# PLACA_01.net
KiCad netlist of a schematic drawn in EAGLE
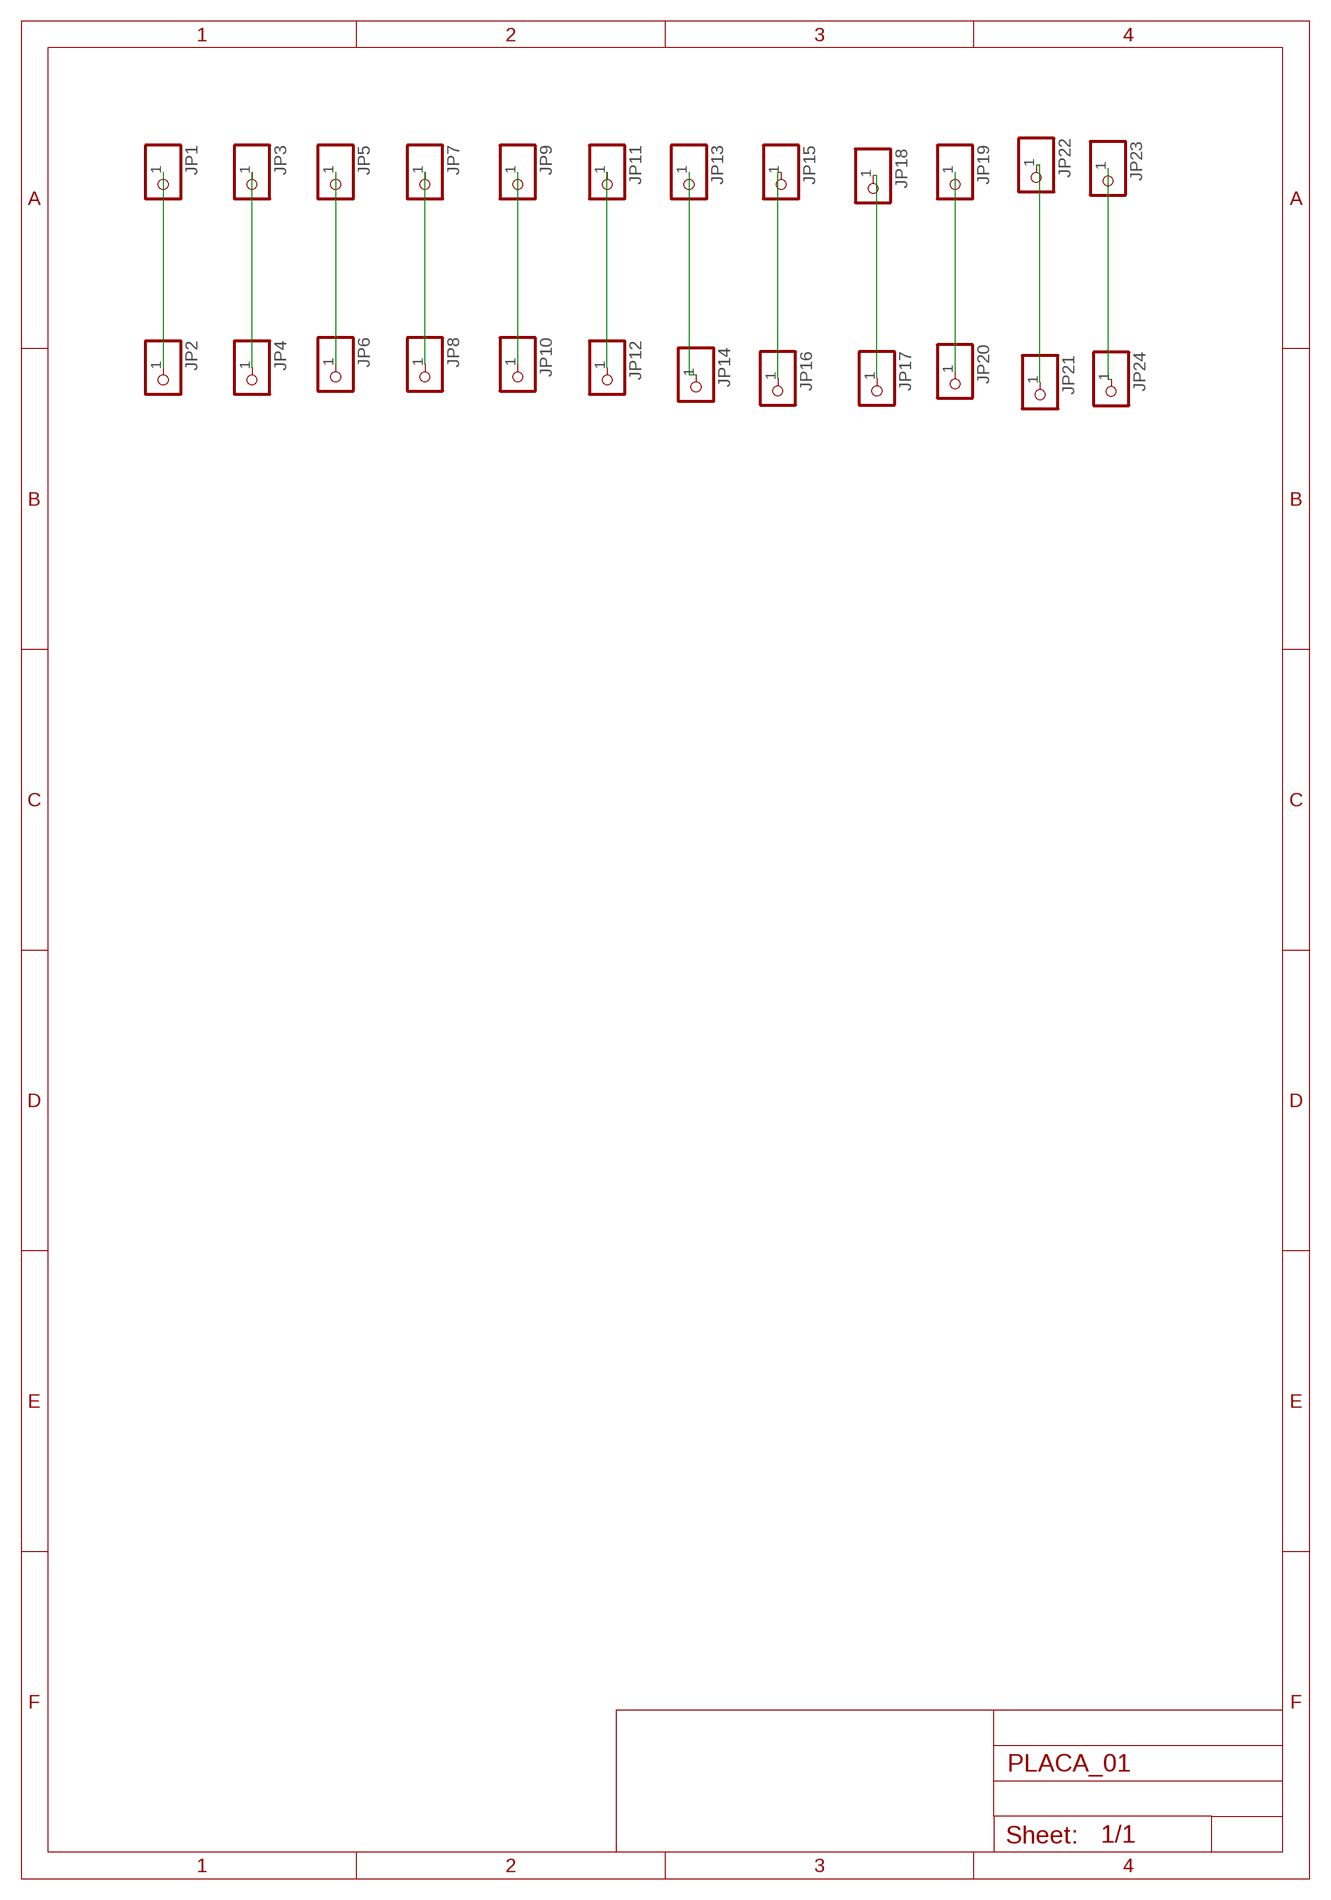
[diagram p0: schematic, sheet 1]

(export (version "E")
  (design (tool "Eeschema 10.0.6"))
  (components
    (comp (ref "JP1")
      (value "PINHD-1X1")
      (footprint "eagle-import:1X01")
      (libsource (lib "eagle-import") (part "PINHD-1X1"))
    )
    (comp (ref "JP2")
      (value "PINHD-1X1")
      (footprint "eagle-import:1X01")
      (libsource (lib "eagle-import") (part "PINHD-1X1"))
    )
    (comp (ref "JP3")
      (value "PINHD-1X1")
      (footprint "eagle-import:1X01")
      (libsource (lib "eagle-import") (part "PINHD-1X1"))
    )
    (comp (ref "JP4")
      (value "PINHD-1X1")
      (footprint "eagle-import:1X01")
      (libsource (lib "eagle-import") (part "PINHD-1X1"))
    )
    (comp (ref "JP5")
      (value "PINHD-1X1")
      (footprint "eagle-import:1X01")
      (libsource (lib "eagle-import") (part "PINHD-1X1"))
    )
    (comp (ref "JP6")
      (value "PINHD-1X1")
      (footprint "eagle-import:1X01")
      (libsource (lib "eagle-import") (part "PINHD-1X1"))
    )
    (comp (ref "JP7")
      (value "PINHD-1X1")
      (footprint "eagle-import:1X01")
      (libsource (lib "eagle-import") (part "PINHD-1X1"))
    )
    (comp (ref "JP8")
      (value "PINHD-1X1")
      (footprint "eagle-import:1X01")
      (libsource (lib "eagle-import") (part "PINHD-1X1"))
    )
    (comp (ref "JP9")
      (value "PINHD-1X1")
      (footprint "eagle-import:1X01")
      (libsource (lib "eagle-import") (part "PINHD-1X1"))
    )
    (comp (ref "JP10")
      (value "PINHD-1X1")
      (footprint "eagle-import:1X01")
      (libsource (lib "eagle-import") (part "PINHD-1X1"))
    )
    (comp (ref "JP11")
      (value "PINHD-1X1")
      (footprint "eagle-import:1X01")
      (libsource (lib "eagle-import") (part "PINHD-1X1"))
    )
    (comp (ref "JP12")
      (value "PINHD-1X1")
      (footprint "eagle-import:1X01")
      (libsource (lib "eagle-import") (part "PINHD-1X1"))
    )
    (comp (ref "JP13")
      (value "PINHD-1X1")
      (footprint "eagle-import:1X01")
      (libsource (lib "eagle-import") (part "PINHD-1X1"))
    )
    (comp (ref "JP14")
      (value "PINHD-1X1")
      (footprint "eagle-import:1X01")
      (libsource (lib "eagle-import") (part "PINHD-1X1"))
    )
    (comp (ref "JP15")
      (value "PINHD-1X1")
      (footprint "eagle-import:1X01")
      (libsource (lib "eagle-import") (part "PINHD-1X1"))
    )
    (comp (ref "JP16")
      (value "PINHD-1X1")
      (footprint "eagle-import:1X01")
      (libsource (lib "eagle-import") (part "PINHD-1X1"))
    )
    (comp (ref "JP17")
      (value "PINHD-1X1")
      (footprint "eagle-import:1X01")
      (libsource (lib "eagle-import") (part "PINHD-1X1"))
    )
    (comp (ref "JP18")
      (value "PINHD-1X1")
      (footprint "eagle-import:1X01")
      (libsource (lib "eagle-import") (part "PINHD-1X1"))
    )
    (comp (ref "JP19")
      (value "PINHD-1X1")
      (footprint "eagle-import:1X01")
      (libsource (lib "eagle-import") (part "PINHD-1X1"))
    )
    (comp (ref "JP20")
      (value "PINHD-1X1")
      (footprint "eagle-import:1X01")
      (libsource (lib "eagle-import") (part "PINHD-1X1"))
    )
    (comp (ref "JP21")
      (value "PINHD-1X1")
      (footprint "eagle-import:1X01")
      (libsource (lib "eagle-import") (part "PINHD-1X1"))
    )
    (comp (ref "JP22")
      (value "PINHD-1X1")
      (footprint "eagle-import:1X01")
      (libsource (lib "eagle-import") (part "PINHD-1X1"))
    )
    (comp (ref "JP23")
      (value "PINHD-1X1")
      (footprint "eagle-import:1X01")
      (libsource (lib "eagle-import") (part "PINHD-1X1"))
    )
    (comp (ref "JP24")
      (value "PINHD-1X1")
      (footprint "eagle-import:1X01")
      (libsource (lib "eagle-import") (part "PINHD-1X1"))
    )
  )
  (nets
    (net (code "1") (name "Net-(JP1-Pad1)") (class "Default")
      (node (ref "JP1") (pin "1") (pinfunction "1_1") (pintype "passive"))
      (node (ref "JP2") (pin "1") (pinfunction "1_1") (pintype "passive"))
    )
    (net (code "2") (name "Net-(JP3-Pad1)") (class "Default")
      (node (ref "JP3") (pin "1") (pinfunction "1_1") (pintype "passive"))
      (node (ref "JP4") (pin "1") (pinfunction "1_1") (pintype "passive"))
    )
    (net (code "3") (name "Net-(JP5-Pad1)") (class "Default")
      (node (ref "JP5") (pin "1") (pinfunction "1_1") (pintype "passive"))
      (node (ref "JP6") (pin "1") (pinfunction "1_1") (pintype "passive"))
    )
    (net (code "4") (name "Net-(JP7-Pad1)") (class "Default")
      (node (ref "JP7") (pin "1") (pinfunction "1_1") (pintype "passive"))
      (node (ref "JP8") (pin "1") (pinfunction "1_1") (pintype "passive"))
    )
    (net (code "5") (name "Net-(JP10-Pad1)") (class "Default")
      (node (ref "JP10") (pin "1") (pinfunction "1_1") (pintype "passive"))
      (node (ref "JP9") (pin "1") (pinfunction "1_1") (pintype "passive"))
    )
    (net (code "6") (name "Net-(JP11-Pad1)") (class "Default")
      (node (ref "JP11") (pin "1") (pinfunction "1_1") (pintype "passive"))
      (node (ref "JP12") (pin "1") (pinfunction "1_1") (pintype "passive"))
    )
    (net (code "7") (name "Net-(JP13-Pad1)") (class "Default")
      (node (ref "JP13") (pin "1") (pinfunction "1_1") (pintype "passive"))
      (node (ref "JP14") (pin "1") (pinfunction "1_1") (pintype "passive"))
    )
    (net (code "8") (name "Net-(JP15-Pad1)") (class "Default")
      (node (ref "JP15") (pin "1") (pinfunction "1_1") (pintype "passive"))
      (node (ref "JP16") (pin "1") (pinfunction "1_1") (pintype "passive"))
    )
    (net (code "9") (name "Net-(JP17-Pad1)") (class "Default")
      (node (ref "JP17") (pin "1") (pinfunction "1_1") (pintype "passive"))
      (node (ref "JP18") (pin "1") (pinfunction "1_1") (pintype "passive"))
    )
    (net (code "10") (name "Net-(JP19-Pad1)") (class "Default")
      (node (ref "JP19") (pin "1") (pinfunction "1_1") (pintype "passive"))
      (node (ref "JP20") (pin "1") (pinfunction "1_1") (pintype "passive"))
    )
    (net (code "11") (name "Net-(JP21-Pad1)") (class "Default")
      (node (ref "JP21") (pin "1") (pinfunction "1_1") (pintype "passive"))
      (node (ref "JP22") (pin "1") (pinfunction "1_1") (pintype "passive"))
    )
    (net (code "12") (name "Net-(JP23-Pad1)") (class "Default")
      (node (ref "JP23") (pin "1") (pinfunction "1_1") (pintype "passive"))
      (node (ref "JP24") (pin "1") (pinfunction "1_1") (pintype "passive"))
    )
  )
)
